# BMS_Slave_Device_R1_5.net
KiCad netlist of a schematic drawn in Altium Designer
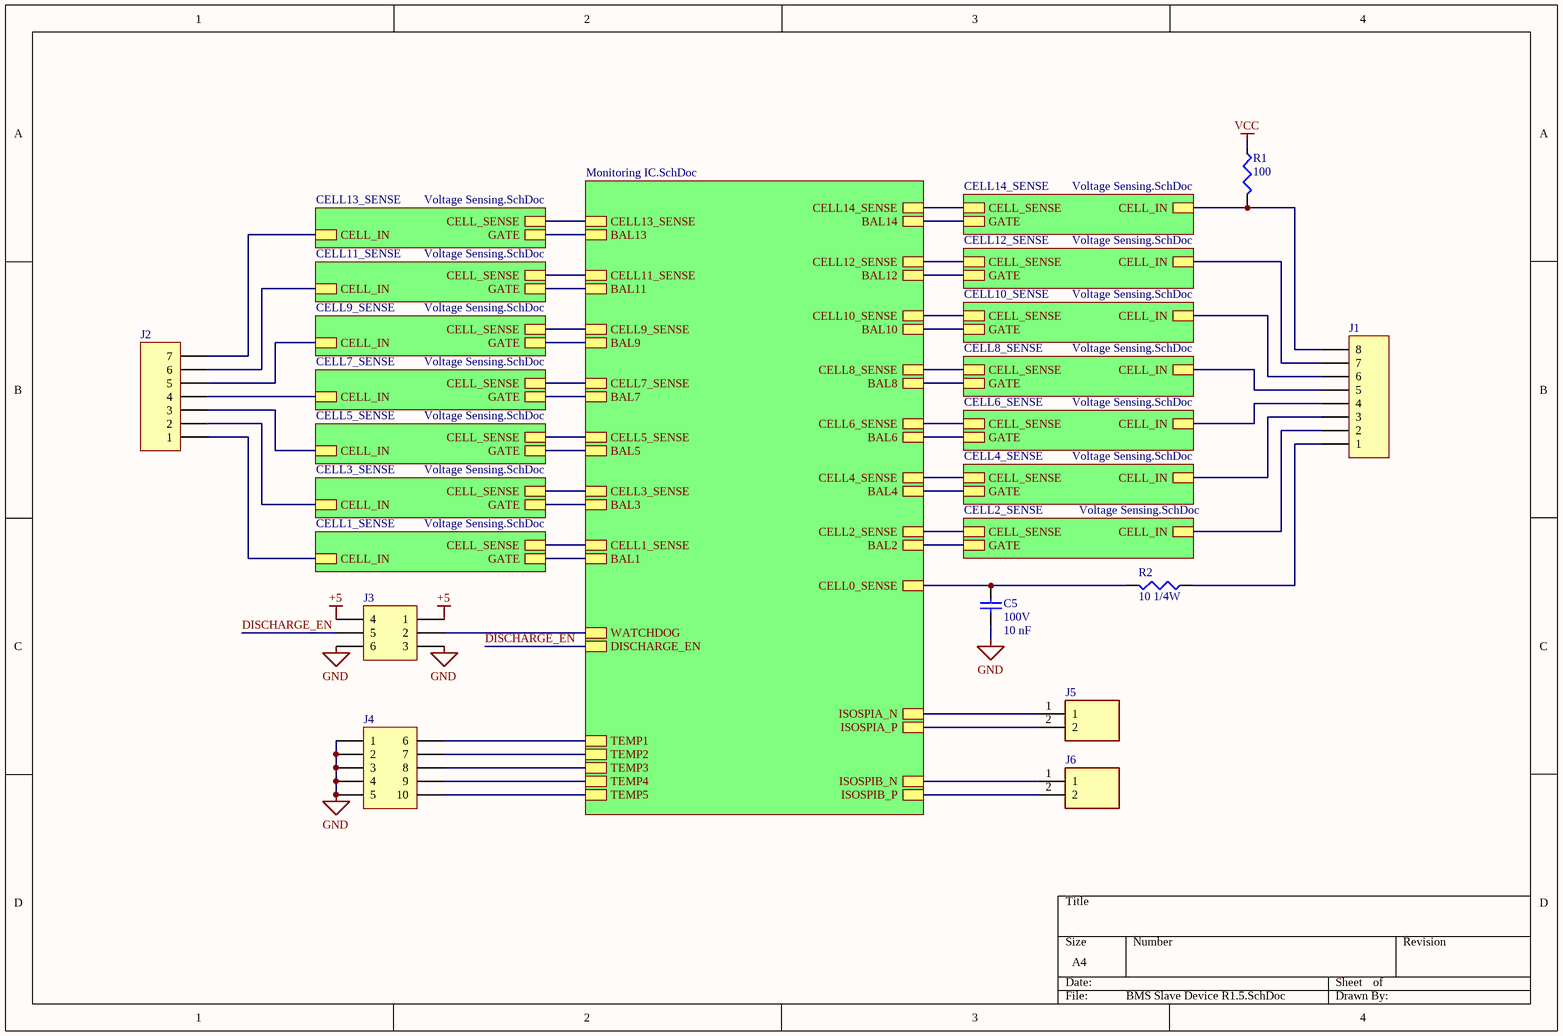
[diagram p0: BMS Slave Device R1.5.SchDoc]

(export (version "E")
  (design (tool "Eeschema 10.0.6"))
  (components
    (comp (ref "C5")
      (value "100V")
      (footprint "6-0805_N")
      (description "Capacitor")
      (fields (field (name "ALTIUM_VALUE") "10 nF") (field (name "PUBLISHER") "Altium Limited"))
      (libsource (lib "Miscellaneous Devices") (part "Cap"))
    )
    (comp (ref "J1")
      (value "Header 8")
      (footprint "HDR1X8")
      (description "Header, 8-Pin")
      (fields (field (name "PUBLISHER") "Altium Limited"))
      (libsource (lib "Miscellaneous Connectors") (part "Header 8"))
    )
    (comp (ref "J2")
      (value "ODD CELLS")
      (footprint "HDR1X7")
      (fields (field (name "PUBLISHER") "Altium Limited"))
      (libsource (lib "Miscellaneous Connectors") (part "Header 7"))
    )
    (comp (ref "J3")
      (value "~")
      (footprint "HDR2X3_CEN")
      (description "Header, 3-Pin, Dual row")
      (fields (field (name "PUBLISHER") "Altium Limited"))
      (libsource (lib "Miscellaneous Connectors") (part "Header 3X2A"))
    )
    (comp (ref "J4")
      (value "THERMISTORS")
      (footprint "HDR2X5_CEN")
      (description "Header, 5-Pin, Dual row")
      (fields (field (name "PUBLISHER") "Altium Limited"))
      (libsource (lib "Miscellaneous Connectors") (part "Header 5X2A"))
    )
    (comp (ref "J5")
      (value "B2B-XH-2__LF__SN_")
      (footprint "BMS Slave Device R1:B2BXH2LFSN")
      (description "Connector")
      (fields
        (field (name "MANUFACTURER_PART_NUMBER") "B2B-XH-2 (LF)(SN)")
        (field (name "RS PART NUMBER") "1755499")
      )
      (libsource (lib "BMS Slave Device R1") (part "B2B-XH-2__LF__SN_"))
    )
    (comp (ref "J6")
      (value "B2B-XH-2__LF__SN_")
      (footprint "BMS Slave Device R1:B2BXH2LFSN")
      (description "Connector")
      (fields
        (field (name "MANUFACTURER_PART_NUMBER") "B2B-XH-2 (LF)(SN)")
        (field (name "RS PART NUMBER") "1755499")
      )
      (libsource (lib "BMS Slave Device R1") (part "B2B-XH-2__LF__SN_"))
    )
    (comp (ref "R1")
      (value "100")
      (footprint "J1-0603")
      (description "Resistor")
      (fields (field (name "Comment") "Res3") (field (name "PUBLISHER") "Altium Limited"))
      (libsource (lib "Miscellaneous Devices") (part "Res3"))
    )
    (comp (ref "R2")
      (value "10 1/4W")
      (footprint "C1206")
      (description "Resistor")
      (fields (field (name "PUBLISHER") "Altium Limited"))
      (libsource (lib "Miscellaneous Devices") (part "Res3"))
    )
  )
  (nets
    (net (code "1") (name "+5") (class "Default")
      (node (ref "J3") (pin "1") (pinfunction "1_1") (pintype "passive"))
      (node (ref "J3") (pin "4") (pinfunction "4_4") (pintype "passive"))
    )
    (net (code "16") (name "/CELL0_SENSE") (class "Default")
      (node (ref "C5") (pin "2") (pinfunction "2_2") (pintype "passive"))
      (node (ref "R2") (pin "1") (pinfunction "1_1") (pintype "passive"))
    )
    (net (code "31") (name "/CELL_IN") (class "Default")
      (node (ref "J1") (pin "2") (pinfunction "2_2") (pintype "passive"))
    )
    (net (code "32") (name "/CELL_IN_1") (class "Default")
      (node (ref "J2") (pin "7") (pinfunction "7_7") (pintype "passive"))
    )
    (net (code "33") (name "/CELL_IN_2") (class "Default")
      (node (ref "J2") (pin "6") (pinfunction "6_6") (pintype "passive"))
    )
    (net (code "34") (name "/CELL_IN_3") (class "Default")
      (node (ref "J2") (pin "5") (pinfunction "5_5") (pintype "passive"))
    )
    (net (code "35") (name "/CELL_IN_4") (class "Default")
      (node (ref "J2") (pin "3") (pinfunction "3_3") (pintype "passive"))
    )
    (net (code "36") (name "/CELL_IN_5") (class "Default")
      (node (ref "J2") (pin "1") (pinfunction "1_1") (pintype "passive"))
    )
    (net (code "37") (name "/CELL_IN_6") (class "Default")
      (node (ref "J2") (pin "2") (pinfunction "2_2") (pintype "passive"))
    )
    (net (code "38") (name "/CELL_IN_7") (class "Default")
      (node (ref "J2") (pin "4") (pinfunction "4_4") (pintype "passive"))
    )
    (net (code "39") (name "/CELL_IN_8") (class "Default")
      (node (ref "J1") (pin "6") (pinfunction "6_6") (pintype "passive"))
    )
    (net (code "40") (name "/CELL_IN_9") (class "Default")
      (node (ref "J1") (pin "5") (pinfunction "5_5") (pintype "passive"))
    )
    (net (code "41") (name "/CELL_IN_10") (class "Default")
      (node (ref "J1") (pin "4") (pinfunction "4_4") (pintype "passive"))
    )
    (net (code "42") (name "/CELL_IN_11") (class "Default")
      (node (ref "J1") (pin "8") (pinfunction "8_8") (pintype "passive"))
      (node (ref "R1") (pin "1") (pinfunction "1_1") (pintype "passive"))
    )
    (net (code "43") (name "/CELL_IN_12") (class "Default")
      (node (ref "J1") (pin "7") (pinfunction "7_7") (pintype "passive"))
    )
    (net (code "44") (name "/CELL_IN_13") (class "Default")
      (node (ref "J1") (pin "3") (pinfunction "3_3") (pintype "passive"))
    )
    (net (code "45") (name "/DISCHARGE_EN") (class "Default")
      (node (ref "J3") (pin "5") (pinfunction "5_5") (pintype "passive"))
    )
    (net (code "46") (name "/ISOSPIA_N") (class "Default")
      (node (ref "J5") (pin "1") (pinfunction "1_1") (pintype "passive"))
    )
    (net (code "47") (name "/ISOSPIA_P") (class "Default")
      (node (ref "J5") (pin "2") (pinfunction "2_2") (pintype "passive"))
    )
    (net (code "48") (name "/ISOSPIB_N") (class "Default")
      (node (ref "J6") (pin "1") (pinfunction "1_1") (pintype "passive"))
    )
    (net (code "49") (name "/ISOSPIB_P") (class "Default")
      (node (ref "J6") (pin "2") (pinfunction "2_2") (pintype "passive"))
    )
    (net (code "50") (name "/TEMP1") (class "Default")
      (node (ref "J4") (pin "6") (pinfunction "6_6") (pintype "passive"))
    )
    (net (code "51") (name "/TEMP2") (class "Default")
      (node (ref "J4") (pin "7") (pinfunction "7_7") (pintype "passive"))
    )
    (net (code "52") (name "/TEMP3") (class "Default")
      (node (ref "J4") (pin "8") (pinfunction "8_8") (pintype "passive"))
    )
    (net (code "53") (name "/TEMP4") (class "Default")
      (node (ref "J4") (pin "9") (pinfunction "9_9") (pintype "passive"))
    )
    (net (code "54") (name "/TEMP5") (class "Default")
      (node (ref "J4") (pin "10") (pinfunction "10_10") (pintype "passive"))
    )
    (net (code "55") (name "/WATCHDOG") (class "Default")
      (node (ref "J3") (pin "2") (pinfunction "2_2") (pintype "passive"))
    )
    (net (code "56") (name "GND") (class "Default")
      (node (ref "C5") (pin "1") (pinfunction "1_1") (pintype "passive"))
      (node (ref "J3") (pin "3") (pinfunction "3_3") (pintype "passive"))
      (node (ref "J3") (pin "6") (pinfunction "6_6") (pintype "passive"))
      (node (ref "J4") (pin "1") (pinfunction "1_1") (pintype "passive"))
      (node (ref "J4") (pin "2") (pinfunction "2_2") (pintype "passive"))
      (node (ref "J4") (pin "3") (pinfunction "3_3") (pintype "passive"))
      (node (ref "J4") (pin "4") (pinfunction "4_4") (pintype "passive"))
      (node (ref "J4") (pin "5") (pinfunction "5_5") (pintype "passive"))
    )
    (net (code "57") (name "Net-(J1-Pad1)") (class "Default")
      (node (ref "J1") (pin "1") (pinfunction "1_1") (pintype "passive"))
      (node (ref "R2") (pin "2") (pinfunction "2_2") (pintype "passive"))
    )
    (net (code "58") (name "VCC") (class "Default")
      (node (ref "R1") (pin "2") (pinfunction "2_2") (pintype "passive"))
    )
  )
)
